# flash.net
KiCad netlist of a schematic drawn in Altium Designer
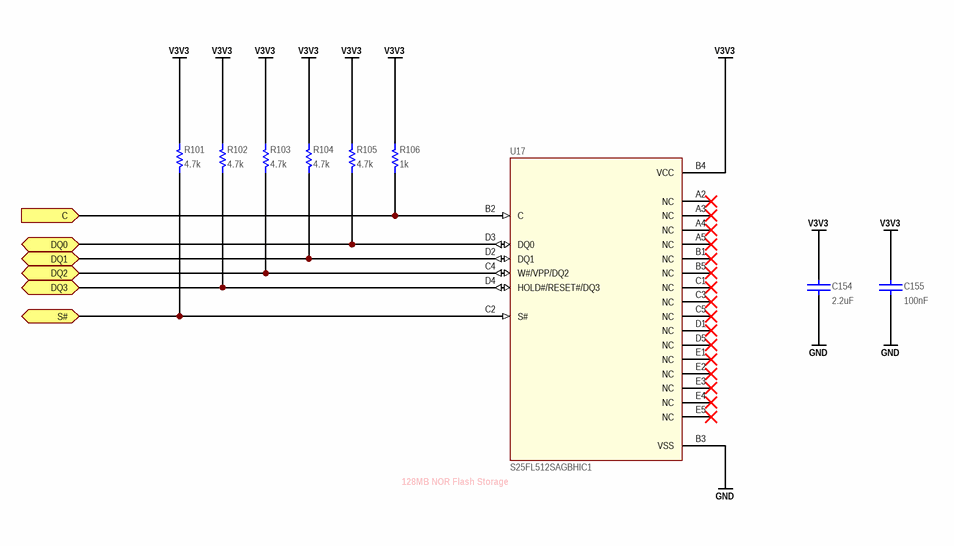
[diagram p0: flash.SchDoc]

(export (version "E")
  (design (tool "Eeschema 10.0.6"))
  (components
    (comp (ref "C154")
      (value "2.2uF")
      (footprint "CAPC160X80X90L20N")
      (description "Ceramic Capacitor 2.2uF ±20% 10V X7R 0603")
      (fields (field (name "MANUFACTURER") "TDK") (field (name "TOLERANCE") "±20%"))
      (libsource (lib "generic") (part "CAP"))
    )
    (comp (ref "C155")
      (value "100nF")
      (footprint "CAPC100X50X55L25N")
      (description "Ceramic Capacitor 100nF ±10% 50V X7R 0402")
      (fields (field (name "MANUFACTURER") "Murata") (field (name "TOLERANCE") "±10%"))
      (libsource (lib "generic") (part "CAP"))
    )
    (comp (ref "R101")
      (value "4.7k")
      (footprint "RESC1005X40N")
      (description "Thick Film Resistor 4.7k ±1% 0.1W 75V 0402")
      (fields (field (name "TOLERANCE") "±1%") (field (name "MANUFACTURER") "Panasonic"))
      (libsource (lib "generic") (part "RES"))
    )
    (comp (ref "R102")
      (value "4.7k")
      (footprint "RESC1005X40N")
      (description "Thick Film Resistor 4.7k ±1% 0.1W 75V 0402")
      (fields (field (name "TOLERANCE") "±1%") (field (name "MANUFACTURER") "Panasonic"))
      (libsource (lib "generic") (part "RES"))
    )
    (comp (ref "R103")
      (value "4.7k")
      (footprint "RESC1005X40N")
      (description "Thick Film Resistor 4.7k ±1% 0.1W 75V 0402")
      (fields (field (name "TOLERANCE") "±1%") (field (name "MANUFACTURER") "Panasonic"))
      (libsource (lib "generic") (part "RES"))
    )
    (comp (ref "R104")
      (value "4.7k")
      (footprint "RESC1005X40N")
      (description "Thick Film Resistor 4.7k ±1% 0.1W 75V 0402")
      (fields (field (name "TOLERANCE") "±1%") (field (name "MANUFACTURER") "Panasonic"))
      (libsource (lib "generic") (part "RES"))
    )
    (comp (ref "R105")
      (value "4.7k")
      (footprint "RESC1005X40N")
      (description "Thick Film Resistor 4.7k ±1% 0.1W 75V 0402")
      (fields (field (name "TOLERANCE") "±1%") (field (name "MANUFACTURER") "Panasonic"))
      (libsource (lib "generic") (part "RES"))
    )
    (comp (ref "R106")
      (value "1k")
      (footprint "RESC1005X40N")
      (description "Thick Film Resistor 1k ±1% 0.1W 50V 0402")
      (fields (field (name "TOLERANCE") "±1%") (field (name "MANUFACTURER") "Panasonic"))
      (libsource (lib "generic") (part "RES"))
    )
    (comp (ref "U17")
      (value "S25FL512SAGBHIC1")
      (footprint "micron:L-PBGA-24")
      (description "1024Mb, 3.3V Serial Flash Memory LBGA24")
      (fields (field (name "MANUFACTURER") "Cypress"))
      (libsource (lib "micron") (part "N25Q00AA13G1240"))
    )
  )
  (nets
    (net (code "1") (name "/C") (class "Default")
      (node (ref "R106") (pin "1") (pinfunction "1_1") (pintype "passive"))
      (node (ref "U17") (pin "B2") (pinfunction "C_B2") (pintype "input"))
    )
    (net (code "2") (name "/DQ0") (class "Default")
      (node (ref "R105") (pin "1") (pinfunction "1_1") (pintype "passive"))
      (node (ref "U17") (pin "D3") (pinfunction "DQ0_D3") (pintype "bidirectional"))
    )
    (net (code "3") (name "/DQ1") (class "Default")
      (node (ref "R104") (pin "1") (pinfunction "1_1") (pintype "passive"))
      (node (ref "U17") (pin "D2") (pinfunction "DQ1_D2") (pintype "bidirectional"))
    )
    (net (code "4") (name "/DQ2") (class "Default")
      (node (ref "R103") (pin "1") (pinfunction "1_1") (pintype "passive"))
      (node (ref "U17") (pin "C4") (pinfunction "W#/VPP/DQ2_C4") (pintype "bidirectional"))
    )
    (net (code "5") (name "/DQ3") (class "Default")
      (node (ref "R102") (pin "1") (pinfunction "1_1") (pintype "passive"))
      (node (ref "U17") (pin "D4") (pinfunction "HOLD#/RESET#/DQ3_D4") (pintype "bidirectional"))
    )
    (net (code "6") (name "/S#") (class "Default")
      (node (ref "R101") (pin "1") (pinfunction "1_1") (pintype "passive"))
      (node (ref "U17") (pin "C2") (pinfunction "S#_C2") (pintype "input"))
    )
    (net (code "7") (name "GND") (class "Default")
      (node (ref "C154") (pin "1") (pinfunction "1_1") (pintype "passive"))
      (node (ref "C155") (pin "1") (pinfunction "1_1") (pintype "passive"))
      (node (ref "U17") (pin "B3") (pinfunction "VSS_B3") (pintype "power_in"))
    )
    (net (code "8") (name "V3V3") (class "Default")
      (node (ref "C154") (pin "2") (pinfunction "2_2") (pintype "passive"))
      (node (ref "C155") (pin "2") (pinfunction "2_2") (pintype "passive"))
      (node (ref "R101") (pin "2") (pinfunction "2_2") (pintype "passive"))
      (node (ref "R102") (pin "2") (pinfunction "2_2") (pintype "passive"))
      (node (ref "R103") (pin "2") (pinfunction "2_2") (pintype "passive"))
      (node (ref "R104") (pin "2") (pinfunction "2_2") (pintype "passive"))
      (node (ref "R105") (pin "2") (pinfunction "2_2") (pintype "passive"))
      (node (ref "R106") (pin "2") (pinfunction "2_2") (pintype "passive"))
      (node (ref "U17") (pin "B4") (pinfunction "VCC_B4") (pintype "power_in"))
    )
    (net (code "9") (name "unconnected-(U17-NC-PadA2)") (class "Default")
      (node (ref "U17") (pin "A2") (pinfunction "NC_A2") (pintype "passive+no_connect"))
    )
    (net (code "10") (name "unconnected-(U17-NC-PadA3)") (class "Default")
      (node (ref "U17") (pin "A3") (pinfunction "NC_A3") (pintype "passive+no_connect"))
    )
    (net (code "11") (name "unconnected-(U17-NC-PadA4)") (class "Default")
      (node (ref "U17") (pin "A4") (pinfunction "NC_A4") (pintype "passive+no_connect"))
    )
    (net (code "12") (name "unconnected-(U17-NC-PadA5)") (class "Default")
      (node (ref "U17") (pin "A5") (pinfunction "NC_A5") (pintype "passive+no_connect"))
    )
    (net (code "13") (name "unconnected-(U17-NC-PadB1)") (class "Default")
      (node (ref "U17") (pin "B1") (pinfunction "NC_B1") (pintype "passive+no_connect"))
    )
    (net (code "14") (name "unconnected-(U17-NC-PadB5)") (class "Default")
      (node (ref "U17") (pin "B5") (pinfunction "NC_B5") (pintype "passive+no_connect"))
    )
    (net (code "15") (name "unconnected-(U17-NC-PadC1)") (class "Default")
      (node (ref "U17") (pin "C1") (pinfunction "NC_C1") (pintype "passive+no_connect"))
    )
    (net (code "16") (name "unconnected-(U17-NC-PadC3)") (class "Default")
      (node (ref "U17") (pin "C3") (pinfunction "NC_C3") (pintype "passive+no_connect"))
    )
    (net (code "17") (name "unconnected-(U17-NC-PadC5)") (class "Default")
      (node (ref "U17") (pin "C5") (pinfunction "NC_C5") (pintype "passive+no_connect"))
    )
    (net (code "18") (name "unconnected-(U17-NC-PadD1)") (class "Default")
      (node (ref "U17") (pin "D1") (pinfunction "NC_D1") (pintype "passive+no_connect"))
    )
    (net (code "19") (name "unconnected-(U17-NC-PadD5)") (class "Default")
      (node (ref "U17") (pin "D5") (pinfunction "NC_D5") (pintype "passive+no_connect"))
    )
    (net (code "20") (name "unconnected-(U17-NC-PadE1)") (class "Default")
      (node (ref "U17") (pin "E1") (pinfunction "NC_E1") (pintype "passive+no_connect"))
    )
    (net (code "21") (name "unconnected-(U17-NC-PadE2)") (class "Default")
      (node (ref "U17") (pin "E2") (pinfunction "NC_E2") (pintype "passive+no_connect"))
    )
    (net (code "22") (name "unconnected-(U17-NC-PadE3)") (class "Default")
      (node (ref "U17") (pin "E3") (pinfunction "NC_E3") (pintype "passive+no_connect"))
    )
    (net (code "23") (name "unconnected-(U17-NC-PadE4)") (class "Default")
      (node (ref "U17") (pin "E4") (pinfunction "NC_E4") (pintype "passive+no_connect"))
    )
    (net (code "24") (name "unconnected-(U17-NC-PadE5)") (class "Default")
      (node (ref "U17") (pin "E5") (pinfunction "NC_E5") (pintype "passive+no_connect"))
    )
  )
)
